# pH_EZO_1.net
KiCad netlist of a schematic drawn in Altium Designer
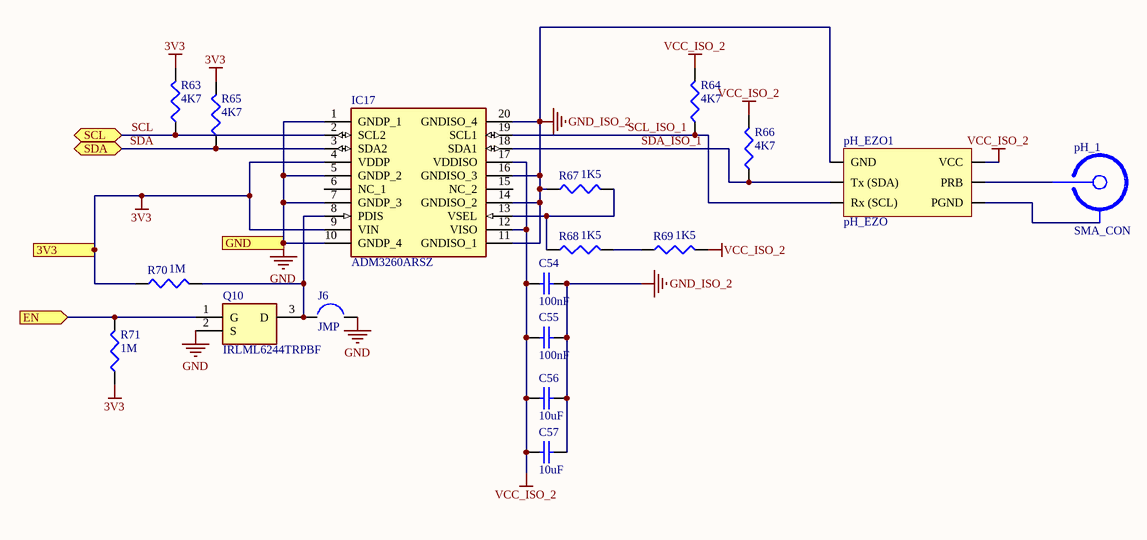
[diagram p0: pH_EZO_1.SchDoc]

(export (version "E")
  (design (tool "Eeschema 10.0.6"))
  (components
    (comp (ref "C54")
      (value "100nF")
      (footprint "1608[0603]")
      (description "Capacitor (Semiconductor SIM Model)")
      (fields (field (name "PUBLISHER") "Altium Limited"))
      (libsource (lib "Miscellaneous Devices") (part "Cap Semi"))
    )
    (comp (ref "C55")
      (value "100nF")
      (footprint "1608[0603]")
      (description "Capacitor (Semiconductor SIM Model)")
      (fields (field (name "PUBLISHER") "Altium Limited"))
      (libsource (lib "Miscellaneous Devices") (part "Cap Semi"))
    )
    (comp (ref "C56")
      (value "10uF")
      (footprint "1608[0603]")
      (description "Capacitor (Semiconductor SIM Model)")
      (fields (field (name "PUBLISHER") "Altium Limited"))
      (libsource (lib "Miscellaneous Devices") (part "Cap Semi"))
    )
    (comp (ref "C57")
      (value "10uF")
      (footprint "1608[0603]")
      (description "Capacitor (Semiconductor SIM Model)")
      (fields (field (name "PUBLISHER") "Altium Limited"))
      (libsource (lib "Miscellaneous Devices") (part "Cap Semi"))
    )
    (comp (ref "IC17")
      (value "ADM3260ARSZ")
      (footprint "SOP65P780X200-20N")
      (description "Integrated Circuit")
      (fields
        (field (name "MOUSER PART NUMBER") "584-ADM3260ARSZ")
        (field (name "RS PART NUMBER") "8319113P")
      )
      (libsource (lib "SamacSys") (part "ADM3260ARSZ"))
    )
    (comp (ref "J6") (value "JMP") (footprint "Jumper") (libsource (lib "SamacSys") (part "JMP")))
    (comp (ref "pH_1")
      (value "SMA_CON")
      (footprint "SamacSys:PCBSMAFRAHT")
      (description "Connector")
      (fields
        (field (name "MANUFACTURER_PART_NUMBER") "PCB.SMAFRA.HT")
        (field (name "MOUSER PART NUMBER") "960-PCB.SMAFRA.HT")
      )
      (libsource (lib "SamacSys") (part "SMA"))
    )
    (comp (ref "pH_EZO1") (value "pH_EZO") (footprint "Ph_ezo") (libsource (lib "SamacSys") (part "pH_EZO")))
    (comp (ref "Q10")
      (value "IRLML6244TRPBF")
      (footprint "SOT95P237X112-3N")
      (description "Transistor")
      (fields
        (field (name "MOUSER PART NUMBER") "942-IRLML6244TRPBF")
        (field (name "RS PART NUMBER") "7377228P")
      )
      (libsource (lib "SamacSys") (part "IRLML6244TRPBF"))
    )
    (comp (ref "R63")
      (value "4K7")
      (footprint "J1-0603")
      (description "Resistor")
      (fields (field (name "PUBLISHER") "Altium Limited"))
      (libsource (lib "Miscellaneous Devices") (part "Res3"))
    )
    (comp (ref "R64")
      (value "4K7")
      (footprint "J1-0603")
      (description "Resistor")
      (fields (field (name "PUBLISHER") "Altium Limited"))
      (libsource (lib "Miscellaneous Devices") (part "Res3"))
    )
    (comp (ref "R65")
      (value "4K7")
      (footprint "J1-0603")
      (description "Resistor")
      (fields (field (name "PUBLISHER") "Altium Limited"))
      (libsource (lib "Miscellaneous Devices") (part "Res3"))
    )
    (comp (ref "R66")
      (value "4K7")
      (footprint "J1-0603")
      (description "Resistor")
      (fields (field (name "PUBLISHER") "Altium Limited"))
      (libsource (lib "Miscellaneous Devices") (part "Res3"))
    )
    (comp (ref "R67")
      (value "1K5")
      (footprint "J1-0603")
      (description "Resistor")
      (fields (field (name "PUBLISHER") "Altium Limited"))
      (libsource (lib "Miscellaneous Devices") (part "Res3"))
    )
    (comp (ref "R68")
      (value "1K5")
      (footprint "J1-0603")
      (description "Resistor")
      (fields (field (name "PUBLISHER") "Altium Limited"))
      (libsource (lib "Miscellaneous Devices") (part "Res3"))
    )
    (comp (ref "R69")
      (value "1K5")
      (footprint "J1-0603")
      (description "Resistor")
      (fields (field (name "PUBLISHER") "Altium Limited"))
      (libsource (lib "Miscellaneous Devices") (part "Res3"))
    )
    (comp (ref "R70")
      (value "1M")
      (footprint "J1-0603")
      (description "Resistor")
      (fields (field (name "PUBLISHER") "Altium Limited"))
      (libsource (lib "Miscellaneous Devices") (part "Res3"))
    )
    (comp (ref "R71")
      (value "1M")
      (footprint "J1-0603")
      (description "Resistor")
      (fields (field (name "PUBLISHER") "Altium Limited"))
      (libsource (lib "Miscellaneous Devices") (part "Res3"))
    )
  )
  (nets
    (net (code "1") (name "/EN") (class "Default")
      (node (ref "Q10") (pin "1") (pinfunction "G_1") (pintype "passive"))
      (node (ref "R71") (pin "2") (pinfunction "2_2") (pintype "passive"))
    )
    (net (code "2") (name "/SCL") (class "Default")
      (node (ref "IC17") (pin "2") (pinfunction "SCL2_2") (pintype "bidirectional"))
      (node (ref "R63") (pin "1") (pinfunction "1_1") (pintype "passive"))
    )
    (net (code "3") (name "/SCL_ISO_1") (class "Default")
      (node (ref "IC17") (pin "19") (pinfunction "SCL1_19") (pintype "bidirectional"))
      (node (ref "R64") (pin "1") (pinfunction "1_1") (pintype "passive"))
      (node (ref "pH_EZO1") (pin "3") (pinfunction "Rx_(SCL)_3") (pintype "passive"))
    )
    (net (code "4") (name "/SDA") (class "Default")
      (node (ref "IC17") (pin "3") (pinfunction "SDA2_3") (pintype "bidirectional"))
      (node (ref "R65") (pin "1") (pinfunction "1_1") (pintype "passive"))
    )
    (net (code "5") (name "/SDA_ISO_1") (class "Default")
      (node (ref "IC17") (pin "18") (pinfunction "SDA1_18") (pintype "bidirectional"))
      (node (ref "R66") (pin "1") (pinfunction "1_1") (pintype "passive"))
      (node (ref "pH_EZO1") (pin "2") (pinfunction "Tx_(SDA)_2") (pintype "passive"))
    )
    (net (code "6") (name "3V3") (class "Default")
      (node (ref "IC17") (pin "4") (pinfunction "VDDP_4") (pintype "power_in"))
      (node (ref "IC17") (pin "9") (pinfunction "VIN_9") (pintype "power_in"))
      (node (ref "R63") (pin "2") (pinfunction "2_2") (pintype "passive"))
      (node (ref "R65") (pin "2") (pinfunction "2_2") (pintype "passive"))
      (node (ref "R70") (pin "1") (pinfunction "1_1") (pintype "passive"))
      (node (ref "R71") (pin "1") (pinfunction "1_1") (pintype "passive"))
    )
    (net (code "7") (name "GND") (class "Default")
      (node (ref "IC17") (pin "1") (pinfunction "GNDP_1_1") (pintype "power_in"))
      (node (ref "IC17") (pin "10") (pinfunction "GNDP_4_10") (pintype "power_in"))
      (node (ref "IC17") (pin "5") (pinfunction "GNDP_2_5") (pintype "power_in"))
      (node (ref "IC17") (pin "7") (pinfunction "GNDP_3_7") (pintype "power_in"))
      (node (ref "J6") (pin "2") (pinfunction "2_2") (pintype "passive"))
      (node (ref "Q10") (pin "2") (pinfunction "S_2") (pintype "passive"))
    )
    (net (code "8") (name "GND_ISO_2") (class "Default")
      (node (ref "C54") (pin "2") (pinfunction "2_2") (pintype "passive"))
      (node (ref "C55") (pin "2") (pinfunction "2_2") (pintype "passive"))
      (node (ref "C56") (pin "2") (pinfunction "2_2") (pintype "passive"))
      (node (ref "C57") (pin "2") (pinfunction "2_2") (pintype "passive"))
      (node (ref "IC17") (pin "11") (pinfunction "GNDISO_1_11") (pintype "power_in"))
      (node (ref "IC17") (pin "14") (pinfunction "GNDISO_2_14") (pintype "power_in"))
      (node (ref "IC17") (pin "16") (pinfunction "GNDISO_3_16") (pintype "power_in"))
      (node (ref "IC17") (pin "20") (pinfunction "GNDISO_4_20") (pintype "power_in"))
      (node (ref "R67") (pin "1") (pinfunction "1_1") (pintype "passive"))
      (node (ref "pH_EZO1") (pin "1") (pinfunction "GND_1") (pintype "passive"))
    )
    (net (code "9") (name "Net-(IC17-PDIS)") (class "Default")
      (node (ref "IC17") (pin "8") (pinfunction "PDIS_8") (pintype "input"))
      (node (ref "J6") (pin "1") (pinfunction "1_1") (pintype "passive"))
      (node (ref "Q10") (pin "3") (pinfunction "D_3") (pintype "passive"))
      (node (ref "R70") (pin "2") (pinfunction "2_2") (pintype "passive"))
    )
    (net (code "10") (name "Net-(IC17-VSEL)") (class "Default")
      (node (ref "IC17") (pin "13") (pinfunction "VSEL_13") (pintype "input"))
      (node (ref "R67") (pin "2") (pinfunction "2_2") (pintype "passive"))
      (node (ref "R68") (pin "1") (pinfunction "1_1") (pintype "passive"))
    )
    (net (code "11") (name "Net-(R68-Pad2)") (class "Default")
      (node (ref "R68") (pin "2") (pinfunction "2_2") (pintype "passive"))
      (node (ref "R69") (pin "1") (pinfunction "1_1") (pintype "passive"))
    )
    (net (code "12") (name "Net-(pH_EZO1-PGND)") (class "Default")
      (node (ref "pH_1") (pin "2") (pintype "passive"))
      (node (ref "pH_EZO1") (pin "6") (pinfunction "PGND_6") (pintype "passive"))
    )
    (net (code "13") (name "Net-(pH_EZO1-PRB)") (class "Default")
      (node (ref "pH_1") (pin "1") (pintype "passive"))
      (node (ref "pH_EZO1") (pin "5") (pinfunction "PRB_5") (pintype "passive"))
    )
    (net (code "14") (name "VCC_ISO_2") (class "Default")
      (node (ref "C54") (pin "1") (pinfunction "1_1") (pintype "passive"))
      (node (ref "C55") (pin "1") (pinfunction "1_1") (pintype "passive"))
      (node (ref "C56") (pin "1") (pinfunction "1_1") (pintype "passive"))
      (node (ref "C57") (pin "1") (pinfunction "1_1") (pintype "passive"))
      (node (ref "IC17") (pin "12") (pinfunction "VISO_12") (pintype "power_in"))
      (node (ref "IC17") (pin "17") (pinfunction "VDDISO_17") (pintype "power_in"))
      (node (ref "R64") (pin "2") (pinfunction "2_2") (pintype "passive"))
      (node (ref "R66") (pin "2") (pinfunction "2_2") (pintype "passive"))
      (node (ref "R69") (pin "2") (pinfunction "2_2") (pintype "passive"))
      (node (ref "pH_EZO1") (pin "4") (pinfunction "VCC_4") (pintype "passive"))
    )
    (net (code "15") (name "unconnected-(IC17-NC_1-Pad6)") (class "Default")
      (node (ref "IC17") (pin "6") (pinfunction "NC_1_6") (pintype "passive"))
    )
    (net (code "16") (name "unconnected-(IC17-NC_2-Pad15)") (class "Default")
      (node (ref "IC17") (pin "15") (pinfunction "NC_2_15") (pintype "passive"))
    )
  )
)
